# bugs.net
KiCad netlist of a schematic drawn in EAGLE
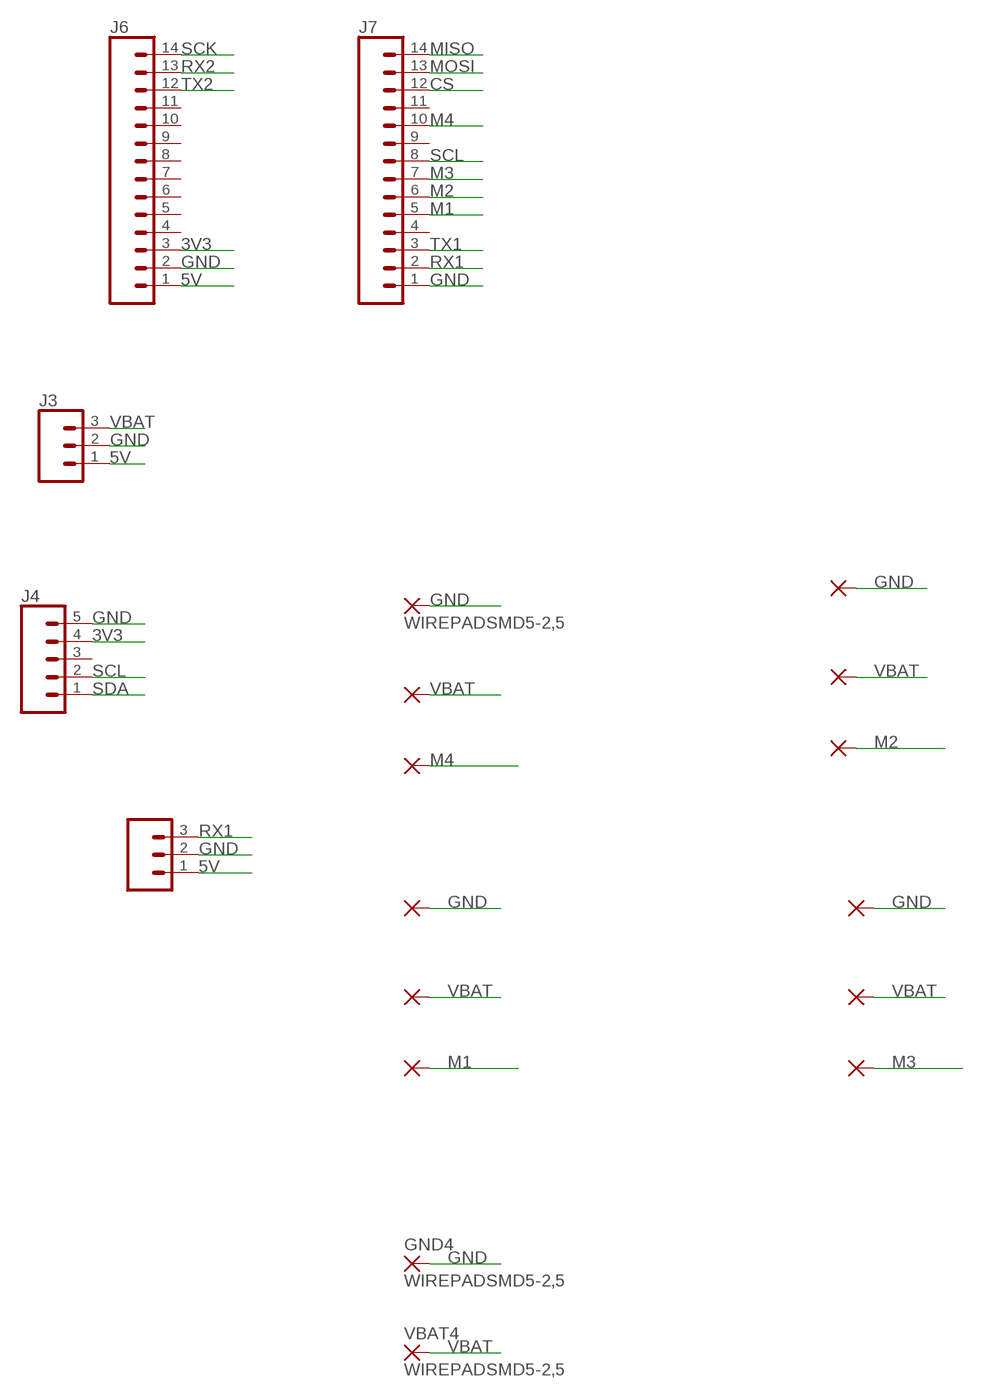
[diagram p0: schematic, sheet 1]

(export (version "E")
  (design (tool "Eeschema 10.0.6"))
  (components
    (comp (ref "GND")
      (value "WIREPADSMD5-2,5")
      (footprint "eagle-import:5-2,5")
      (libsource (lib "eagle-import") (part "WIREPADSMD5-2,5"))
    )
    (comp (ref "GND1")
      (value "WIREPADSMD5-2,5")
      (footprint "eagle-import:5-2,5")
      (libsource (lib "eagle-import") (part "WIREPADSMD5-2,5"))
    )
    (comp (ref "GND2")
      (value "WIREPADSMD5-2,5")
      (footprint "eagle-import:5-2,5")
      (libsource (lib "eagle-import") (part "WIREPADSMD5-2,5"))
    )
    (comp (ref "GND3")
      (value "WIREPADSMD5-2,5")
      (footprint "eagle-import:5-2,5")
      (libsource (lib "eagle-import") (part "WIREPADSMD5-2,5"))
    )
    (comp (ref "GND4")
      (value "WIREPADSMD5-2,5")
      (footprint "eagle-import:5-2,5")
      (libsource (lib "eagle-import") (part "WIREPADSMD5-2,5"))
    )
    (comp (ref "J3")
      (value "CONN_031X03_NO_SILK")
      (footprint "eagle-import:1X03_NO_SILK")
      (libsource (lib "eagle-import") (part "CONN_031X03_NO_SILK"))
    )
    (comp (ref "J4")
      (value "CONN_05NO_SILK")
      (footprint "eagle-import:1X05_NO_SILK")
      (libsource (lib "eagle-import") (part "CONN_05NO_SILK"))
    )
    (comp (ref "J5")
      (value "CONN_031X03_NO_SILK")
      (footprint "eagle-import:1X03_NO_SILK")
      (libsource (lib "eagle-import") (part "CONN_031X03_NO_SILK"))
    )
    (comp (ref "J6")
      (value "CONN_14NO_SILK")
      (footprint "eagle-import:1X14_NO_SILK")
      (libsource (lib "eagle-import") (part "CONN_14NO_SILK"))
    )
    (comp (ref "J7")
      (value "CONN_14NO_SILK")
      (footprint "eagle-import:1X14_NO_SILK")
      (libsource (lib "eagle-import") (part "CONN_14NO_SILK"))
    )
    (comp (ref "M1")
      (value "WIREPADSMD5-2,5")
      (footprint "eagle-import:5-2,5")
      (libsource (lib "eagle-import") (part "WIREPADSMD5-2,5"))
    )
    (comp (ref "M2")
      (value "WIREPADSMD5-2,5")
      (footprint "eagle-import:5-2,5")
      (libsource (lib "eagle-import") (part "WIREPADSMD5-2,5"))
    )
    (comp (ref "M3")
      (value "WIREPADSMD5-2,5")
      (footprint "eagle-import:5-2,5")
      (libsource (lib "eagle-import") (part "WIREPADSMD5-2,5"))
    )
    (comp (ref "M4")
      (value "WIREPADSMD5-2,5")
      (footprint "eagle-import:5-2,5")
      (libsource (lib "eagle-import") (part "WIREPADSMD5-2,5"))
    )
    (comp (ref "VBAT")
      (value "WIREPADSMD5-2,5")
      (footprint "eagle-import:5-2,5")
      (libsource (lib "eagle-import") (part "WIREPADSMD5-2,5"))
    )
    (comp (ref "VBAT1")
      (value "WIREPADSMD5-2,5")
      (footprint "eagle-import:5-2,5")
      (libsource (lib "eagle-import") (part "WIREPADSMD5-2,5"))
    )
    (comp (ref "VBAT2")
      (value "WIREPADSMD5-2,5")
      (footprint "eagle-import:5-2,5")
      (libsource (lib "eagle-import") (part "WIREPADSMD5-2,5"))
    )
    (comp (ref "VBAT3")
      (value "WIREPADSMD5-2,5")
      (footprint "eagle-import:5-2,5")
      (libsource (lib "eagle-import") (part "WIREPADSMD5-2,5"))
    )
    (comp (ref "VBAT4")
      (value "WIREPADSMD5-2,5")
      (footprint "eagle-import:5-2,5")
      (libsource (lib "eagle-import") (part "WIREPADSMD5-2,5"))
    )
  )
  (nets
    (net (code "1") (name "/3V3") (class "Default")
      (node (ref "J4") (pin "4") (pinfunction "4_4") (pintype "passive"))
      (node (ref "J6") (pin "3") (pinfunction "3_3") (pintype "passive"))
    )
    (net (code "2") (name "/5V") (class "Default")
      (node (ref "J3") (pin "1") (pinfunction "1_1") (pintype "passive"))
      (node (ref "J5") (pin "1") (pinfunction "1_1") (pintype "passive"))
      (node (ref "J6") (pin "1") (pinfunction "1_1") (pintype "passive"))
    )
    (net (code "3") (name "/CS") (class "Default")
      (node (ref "J7") (pin "12") (pinfunction "12_12") (pintype "passive"))
    )
    (net (code "4") (name "/GND") (class "Default")
      (node (ref "GND") (pin "1") (pinfunction "P_1") (pintype "passive"))
      (node (ref "GND1") (pin "1") (pinfunction "P_1") (pintype "passive"))
      (node (ref "GND2") (pin "1") (pinfunction "P_1") (pintype "passive"))
      (node (ref "GND3") (pin "1") (pinfunction "P_1") (pintype "passive"))
      (node (ref "GND4") (pin "1") (pinfunction "P_1") (pintype "passive"))
      (node (ref "J3") (pin "2") (pinfunction "2_2") (pintype "passive"))
      (node (ref "J4") (pin "5") (pinfunction "5_5") (pintype "passive"))
      (node (ref "J5") (pin "2") (pinfunction "2_2") (pintype "passive"))
      (node (ref "J6") (pin "2") (pinfunction "2_2") (pintype "passive"))
      (node (ref "J7") (pin "1") (pinfunction "1_1") (pintype "passive"))
    )
    (net (code "5") (name "/M1") (class "Default")
      (node (ref "J7") (pin "5") (pinfunction "5_5") (pintype "passive"))
      (node (ref "M1") (pin "1") (pinfunction "P_1") (pintype "passive"))
    )
    (net (code "6") (name "/M2") (class "Default")
      (node (ref "J7") (pin "6") (pinfunction "6_6") (pintype "passive"))
      (node (ref "M2") (pin "1") (pinfunction "P_1") (pintype "passive"))
    )
    (net (code "7") (name "/M3") (class "Default")
      (node (ref "J7") (pin "7") (pinfunction "7_7") (pintype "passive"))
      (node (ref "M3") (pin "1") (pinfunction "P_1") (pintype "passive"))
    )
    (net (code "8") (name "/M4") (class "Default")
      (node (ref "J7") (pin "10") (pinfunction "10_10") (pintype "passive"))
      (node (ref "M4") (pin "1") (pinfunction "P_1") (pintype "passive"))
    )
    (net (code "9") (name "/MISO") (class "Default")
      (node (ref "J7") (pin "14") (pinfunction "14_14") (pintype "passive"))
    )
    (net (code "10") (name "/MOSI") (class "Default")
      (node (ref "J7") (pin "13") (pinfunction "13_13") (pintype "passive"))
    )
    (net (code "11") (name "/RX1") (class "Default")
      (node (ref "J5") (pin "3") (pinfunction "3_3") (pintype "passive"))
      (node (ref "J7") (pin "2") (pinfunction "2_2") (pintype "passive"))
    )
    (net (code "12") (name "/RX2") (class "Default")
      (node (ref "J6") (pin "13") (pinfunction "13_13") (pintype "passive"))
    )
    (net (code "13") (name "/SCK") (class "Default")
      (node (ref "J6") (pin "14") (pinfunction "14_14") (pintype "passive"))
    )
    (net (code "14") (name "/SCL") (class "Default")
      (node (ref "J4") (pin "2") (pinfunction "2_2") (pintype "passive"))
      (node (ref "J7") (pin "8") (pinfunction "8_8") (pintype "passive"))
    )
    (net (code "15") (name "/SDA") (class "Default")
      (node (ref "J4") (pin "1") (pinfunction "1_1") (pintype "passive"))
    )
    (net (code "16") (name "/TX1") (class "Default")
      (node (ref "J7") (pin "3") (pinfunction "3_3") (pintype "passive"))
    )
    (net (code "17") (name "/TX2") (class "Default")
      (node (ref "J6") (pin "12") (pinfunction "12_12") (pintype "passive"))
    )
    (net (code "18") (name "/VBAT") (class "Default")
      (node (ref "J3") (pin "3") (pinfunction "3_3") (pintype "passive"))
      (node (ref "VBAT") (pin "1") (pinfunction "P_1") (pintype "passive"))
      (node (ref "VBAT1") (pin "1") (pinfunction "P_1") (pintype "passive"))
      (node (ref "VBAT2") (pin "1") (pinfunction "P_1") (pintype "passive"))
      (node (ref "VBAT3") (pin "1") (pinfunction "P_1") (pintype "passive"))
      (node (ref "VBAT4") (pin "1") (pinfunction "P_1") (pintype "passive"))
    )
    (net (code "19") (name "unconnected-(J4-Pad3)") (class "Default")
      (node (ref "J4") (pin "3") (pinfunction "3_3") (pintype "passive"))
    )
    (net (code "20") (name "unconnected-(J6-Pad4)") (class "Default")
      (node (ref "J6") (pin "4") (pinfunction "4_4") (pintype "passive"))
    )
    (net (code "21") (name "unconnected-(J6-Pad5)") (class "Default")
      (node (ref "J6") (pin "5") (pinfunction "5_5") (pintype "passive"))
    )
    (net (code "22") (name "unconnected-(J6-Pad6)") (class "Default")
      (node (ref "J6") (pin "6") (pinfunction "6_6") (pintype "passive"))
    )
    (net (code "23") (name "unconnected-(J6-Pad7)") (class "Default")
      (node (ref "J6") (pin "7") (pinfunction "7_7") (pintype "passive"))
    )
    (net (code "24") (name "unconnected-(J6-Pad8)") (class "Default")
      (node (ref "J6") (pin "8") (pinfunction "8_8") (pintype "passive"))
    )
    (net (code "25") (name "unconnected-(J6-Pad9)") (class "Default")
      (node (ref "J6") (pin "9") (pinfunction "9_9") (pintype "passive"))
    )
    (net (code "26") (name "unconnected-(J6-Pad10)") (class "Default")
      (node (ref "J6") (pin "10") (pinfunction "10_10") (pintype "passive"))
    )
    (net (code "27") (name "unconnected-(J6-Pad11)") (class "Default")
      (node (ref "J6") (pin "11") (pinfunction "11_11") (pintype "passive"))
    )
    (net (code "28") (name "unconnected-(J7-Pad4)") (class "Default")
      (node (ref "J7") (pin "4") (pinfunction "4_4") (pintype "passive"))
    )
    (net (code "29") (name "unconnected-(J7-Pad9)") (class "Default")
      (node (ref "J7") (pin "9") (pinfunction "9_9") (pintype "passive"))
    )
    (net (code "30") (name "unconnected-(J7-Pad11)") (class "Default")
      (node (ref "J7") (pin "11") (pinfunction "11_11") (pintype "passive"))
    )
  )
)
